# Snap-Off.net
KiCad netlist of a schematic drawn in Altium Designer
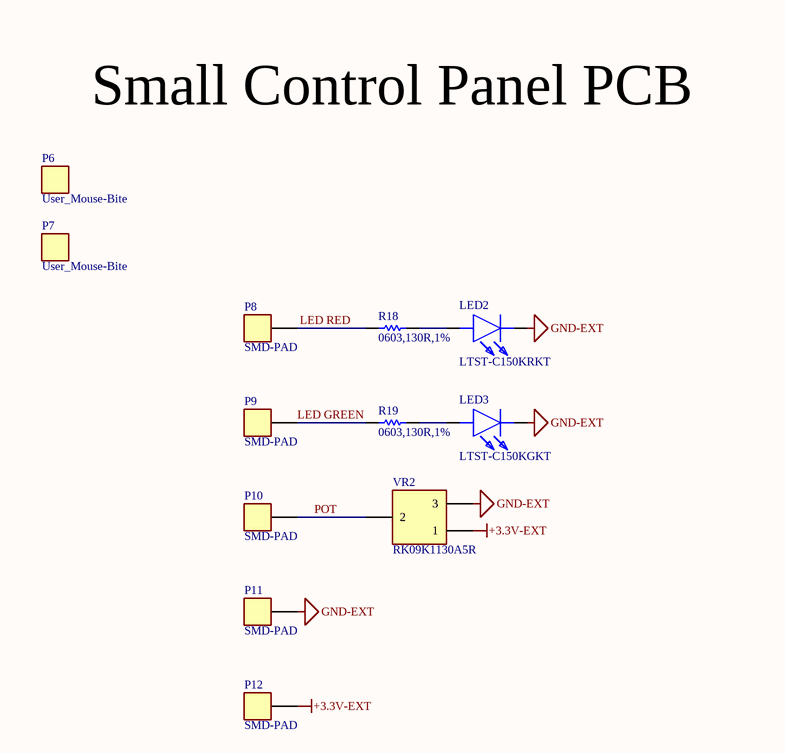
[diagram p0: Snap-Off.SchDoc]

(export (version "E")
  (design (tool "Eeschema 10.0.6"))
  (components
    (comp (ref "LED2")
      (value "LTST-C150KRKT")
      (footprint "LEDC3216X120N")
      (description "20mA 54mcd Water Clear -30℃~+85℃ 624nm Red 130° 62.5mW 2V 1206 LED Indication - Discrete ROHS")
      (fields
        (field (name "MOUSER PART NUMBER") "859-LTST-C150KRKT")
        (field (name "LCSC PART NUMBER") "C125086")
      )
      (libsource (lib "LC-SchLib") (part "LTST-C150KRKT"))
    )
    (comp (ref "LED3")
      (value "LTST-C150KGKT")
      (footprint "LEDC3216X120N")
      (fields
        (field (name "MOUSER PART NUMBER") "859-LTST-C150KGKT")
        (field (name "LCSC PART NUMBER") "C125085")
      )
      (libsource (lib "LC-SchLib") (part "LTST-C150KGKT"))
    )
    (comp (ref "P6")
      (value "User_Mouse-Bite")
      (footprint "mouse-bite-3mm-slot")
      (description "3mm Mouse Bites")
      (libsource (lib "LC-SchLib") (part "User_Mouse-Bite"))
    )
    (comp (ref "P7")
      (value "User_Mouse-Bite")
      (footprint "mouse-bite-3mm-slot")
      (description "3mm Mouse Bites")
      (libsource (lib "LC-SchLib") (part "User_Mouse-Bite"))
    )
    (comp (ref "P8")
      (value "SMD-PAD")
      (footprint "USER_SMD-PAD")
      (description "SMD Pad for 18-22 AWG wire")
      (libsource (lib "LC-SchLib") (part "SMD-PAD"))
    )
    (comp (ref "P9")
      (value "SMD-PAD")
      (footprint "USER_SMD-PAD")
      (description "SMD Pad for 18-22 AWG wire")
      (libsource (lib "LC-SchLib") (part "SMD-PAD"))
    )
    (comp (ref "P10")
      (value "SMD-PAD")
      (footprint "USER_SMD-PAD")
      (description "SMD Pad for 18-22 AWG wire")
      (libsource (lib "LC-SchLib") (part "SMD-PAD"))
    )
    (comp (ref "P11")
      (value "SMD-PAD")
      (footprint "USER_SMD-PAD")
      (description "SMD Pad for 18-22 AWG wire")
      (libsource (lib "LC-SchLib") (part "SMD-PAD"))
    )
    (comp (ref "P12")
      (value "SMD-PAD")
      (footprint "USER_SMD-PAD")
      (description "SMD Pad for 18-22 AWG wire")
      (libsource (lib "LC-SchLib") (part "SMD-PAD"))
    )
    (comp (ref "R18")
      (value "0603,130R,1%")
      (footprint "RESC1608X55N")
      (description "130 Ohms ±1% 0.1W, 1/10W Chip Resistor 0603 (1608 Metric) Moisture Resistant Thick Film")
      (fields
        (field (name "MANUFACTURER_PART_NUMBER") "RC0603FR-07130RL")
        (field (name "LCSC PART NUMBER") "C141677")
      )
      (libsource (lib "LC-SchLib") (part "RC0603FR-07130RL"))
    )
    (comp (ref "R19")
      (value "0603,130R,1%")
      (footprint "RESC1608X55N")
      (description "130 Ohms ±1% 0.1W, 1/10W Chip Resistor 0603 (1608 Metric) Moisture Resistant Thick Film")
      (fields
        (field (name "MANUFACTURER_PART_NUMBER") "RC0603FR-07130RL")
        (field (name "LCSC PART NUMBER") "C141677")
      )
      (libsource (lib "LC-SchLib") (part "RC0603FR-07130RL"))
    )
    (comp (ref "VR2")
      (value "RK09K1130A5R")
      (footprint "RES-ADJ-TH_RK09D1130C4G")
      (description "±20% 50mW 5kΩ Through Hole Potentiometers, Variable Resistors ROHS")
      (fields
        (field (name "MANUFACTURER_PART_NUMBER") "RK09K1130AV7")
        (field (name "MOUSER PART NUMBER") "688-RK09K1130AV7")
      )
      (libsource (lib "LC-SchLib") (part "RK09K1130A5R"))
    )
  )
  (nets
    (net (code "1") (name "+3.3V-EXT") (class "Default")
      (node (ref "P12") (pin "1") (pinfunction "1_1") (pintype "passive"))
      (node (ref "VR2") (pin "1") (pinfunction "1_1") (pintype "passive"))
    )
    (net (code "2") (name "/LED GREEN") (class "Default")
      (node (ref "P9") (pin "1") (pinfunction "1_1") (pintype "passive"))
      (node (ref "R19") (pin "1") (pinfunction "1_1") (pintype "passive"))
    )
    (net (code "3") (name "/LED RED") (class "Default")
      (node (ref "P8") (pin "1") (pinfunction "1_1") (pintype "passive"))
      (node (ref "R18") (pin "1") (pinfunction "1_1") (pintype "passive"))
    )
    (net (code "4") (name "/POT") (class "Default")
      (node (ref "P10") (pin "1") (pinfunction "1_1") (pintype "passive"))
      (node (ref "VR2") (pin "2") (pinfunction "2_2") (pintype "passive"))
    )
    (net (code "5") (name "GND-EXT") (class "Default")
      (node (ref "LED2") (pin "1") (pinfunction "K_1") (pintype "passive"))
      (node (ref "LED3") (pin "1") (pinfunction "K_1") (pintype "passive"))
      (node (ref "P11") (pin "1") (pinfunction "1_1") (pintype "passive"))
      (node (ref "VR2") (pin "3") (pinfunction "3_3") (pintype "passive"))
    )
    (net (code "6") (name "Net-(LED2-A)") (class "Default")
      (node (ref "LED2") (pin "2") (pinfunction "A_2") (pintype "passive"))
      (node (ref "R18") (pin "2") (pinfunction "2_2") (pintype "passive"))
    )
    (net (code "7") (name "Net-(LED3-A)") (class "Default")
      (node (ref "LED3") (pin "2") (pinfunction "A_2") (pintype "passive"))
      (node (ref "R19") (pin "2") (pinfunction "2_2") (pintype "passive"))
    )
  )
)
